# Kinen_Expansion.net
KiCad netlist of a schematic drawn in Altium Designer
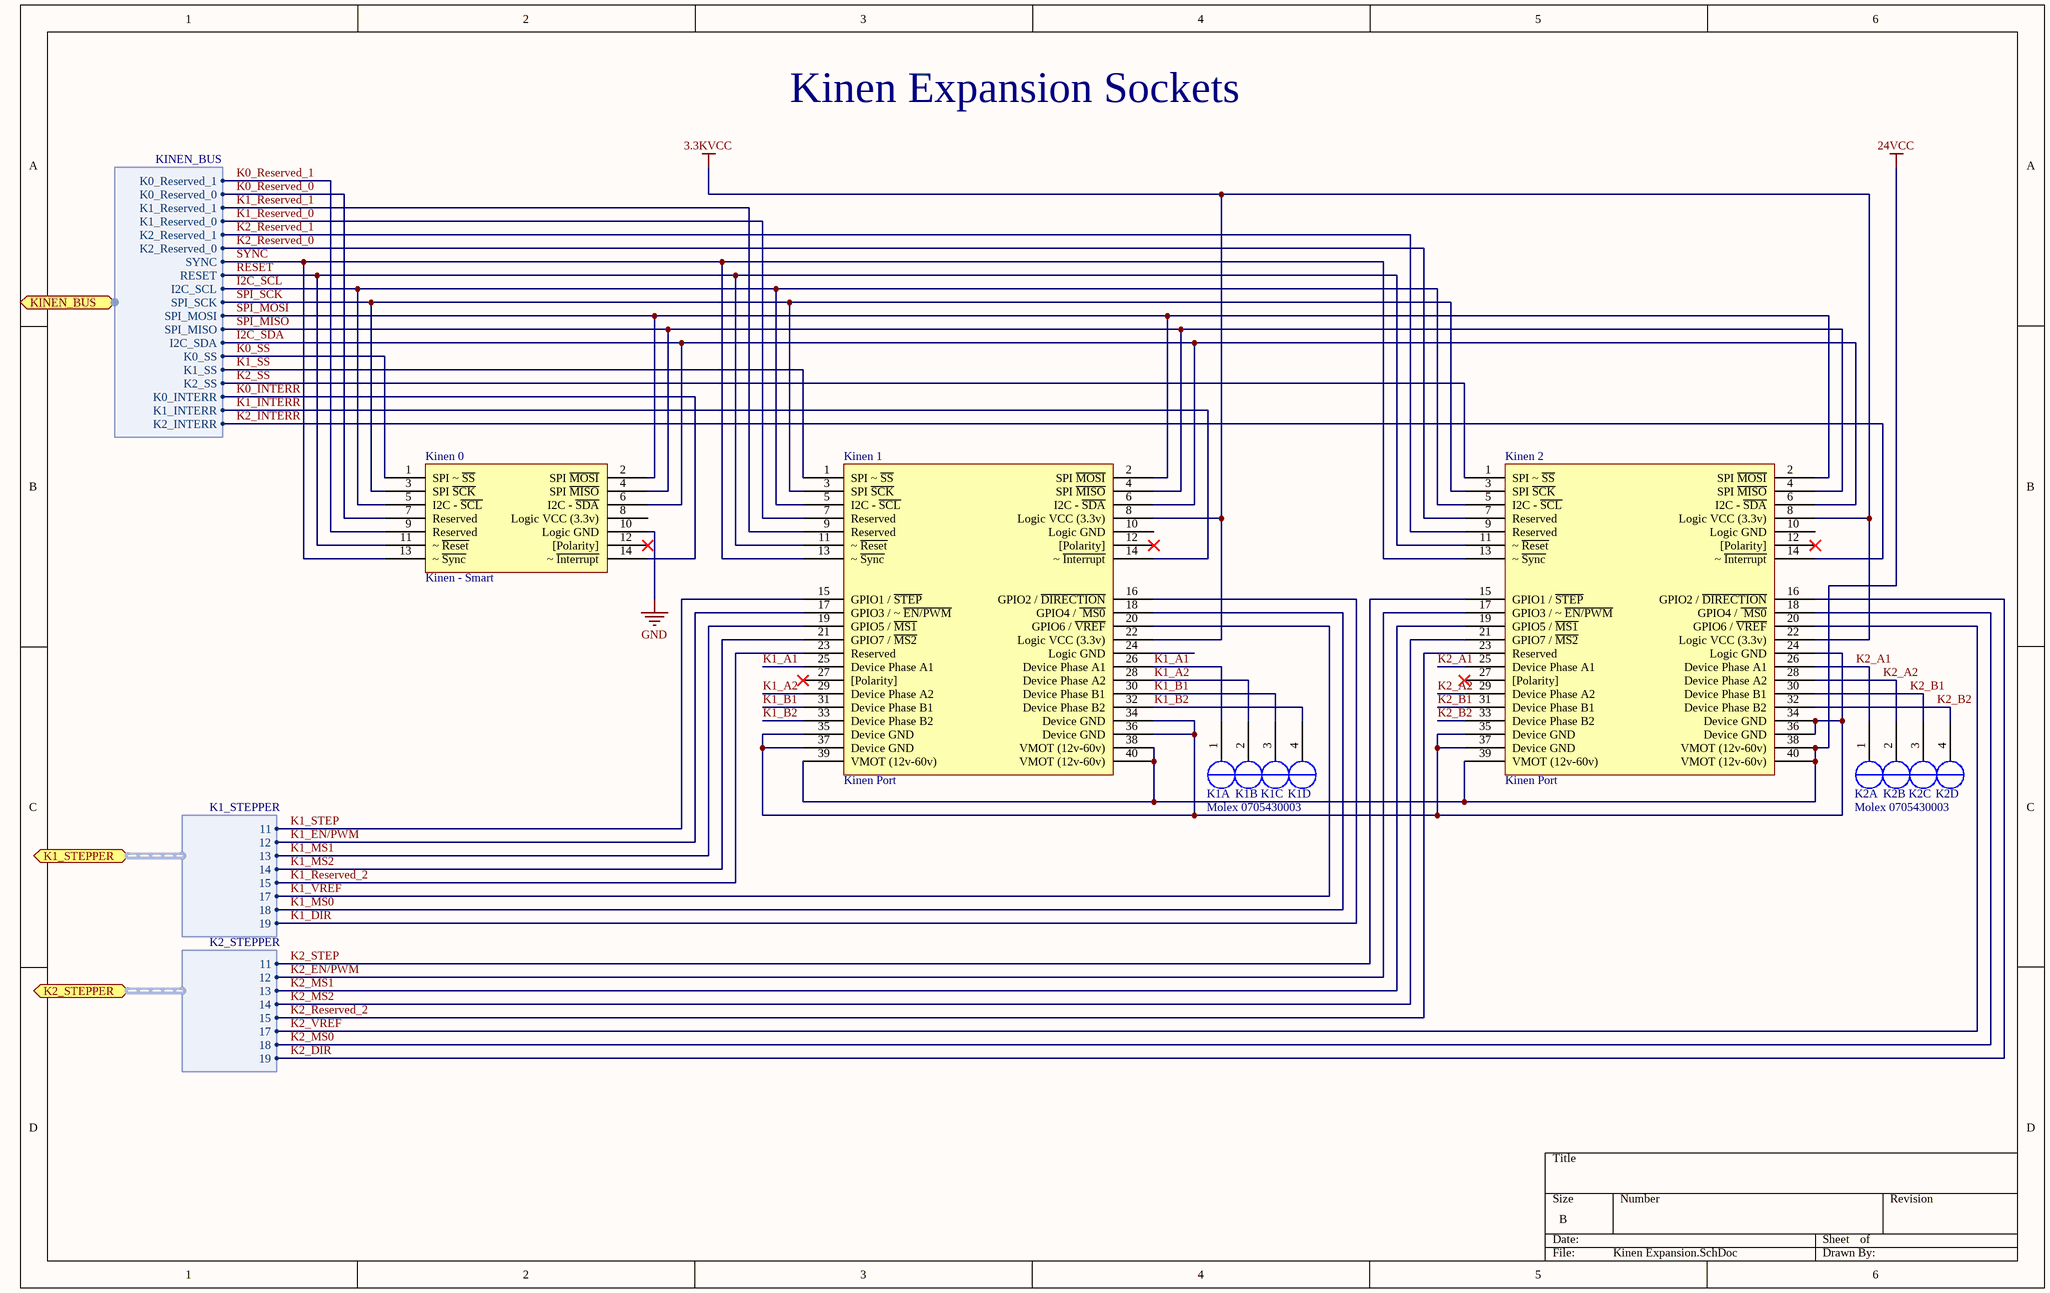
[diagram p0: Kinen Expansion.SchDoc]

(export (version "E")
  (design (tool "Eeschema 10.0.6"))
  (components
    (comp (ref "K1")
      (value "Molex 0705430003")
      (footprint "Molex 0705430003")
      (description "Molex 4 Pin Clip Connector")
      (libsource (lib "") (part "Molex 0705430003 Alt_3"))
    )
    (comp (ref "K2")
      (value "Molex 0705430003")
      (footprint "Molex 0705430003")
      (description "Molex 4 Pin Clip Connector")
      (libsource (lib "ZMBo Schematic Library") (part "Molex 0705430003 Alt"))
    )
    (comp (ref "Kinen 0")
      (value "Kinen - Smart")
      (footprint "Kinen Port - Smart - MOBO")
      (libsource (lib "ZMBo Schematic Library") (part "Kinen - Smart"))
    )
    (comp (ref "Kinen 1")
      (value "Kinen Port")
      (footprint "Kinen Port - MOBO")
      (libsource (lib "ZMBo Schematic Library") (part "Kinen Device NEW"))
    )
    (comp (ref "Kinen 2")
      (value "Kinen Port")
      (footprint "Kinen Port - MOBO")
      (libsource (lib "ZMBo Schematic Library") (part "Kinen Device NEW"))
    )
  )
  (nets
    (net (code "4") (name "/I2C_SCL") (class "Default")
      (node (ref "Kinen 0") (pin "5") (pinfunction "I2C_-_~{SCL}_5") (pintype "passive"))
      (node (ref "Kinen 1") (pin "5") (pinfunction "I2C_-_~{SCL}_5") (pintype "passive"))
      (node (ref "Kinen 2") (pin "5") (pinfunction "I2C_-_~{SCL}_5") (pintype "passive"))
    )
    (net (code "5") (name "/I2C_SDA") (class "Default")
      (node (ref "Kinen 0") (pin "6") (pinfunction "I2C_-_~{SDA}_6") (pintype "passive"))
      (node (ref "Kinen 1") (pin "6") (pinfunction "I2C_-_~{SDA}_6") (pintype "passive"))
      (node (ref "Kinen 2") (pin "6") (pinfunction "I2C_-_~{SDA}_6") (pintype "passive"))
    )
    (net (code "6") (name "/K0_INTERR") (class "Default")
      (node (ref "Kinen 0") (pin "14") (pinfunction "~_~{Interrupt}_14") (pintype "passive"))
    )
    (net (code "7") (name "/K0_Reserved_0") (class "Default")
      (node (ref "Kinen 0") (pin "7") (pinfunction "Reserved_7") (pintype "passive"))
    )
    (net (code "8") (name "/K0_Reserved_1") (class "Default")
      (node (ref "Kinen 0") (pin "9") (pinfunction "Reserved_9") (pintype "passive"))
    )
    (net (code "9") (name "/K0_SS") (class "Default")
      (node (ref "Kinen 0") (pin "1") (pinfunction "SPI_~_~{SS}_1") (pintype "passive"))
    )
    (net (code "10") (name "/K1_A1") (class "Default")
      (node (ref "K1") (pin "1") (pinfunction "OUT2B_1") (pintype "passive"))
      (node (ref "Kinen 1") (pin "25") (pinfunction "Device_Phase_A1_25") (pintype "passive"))
      (node (ref "Kinen 1") (pin "26") (pinfunction "Device_Phase_A1_26") (pintype "passive"))
    )
    (net (code "11") (name "/K1_A2") (class "Default")
      (node (ref "K1") (pin "2") (pinfunction "OUT2A_2") (pintype "passive"))
      (node (ref "Kinen 1") (pin "28") (pinfunction "Device_Phase_A2_28") (pintype "passive"))
      (node (ref "Kinen 1") (pin "29") (pinfunction "Device_Phase_A2_29") (pintype "passive"))
    )
    (net (code "12") (name "/K1_B1") (class "Default")
      (node (ref "K1") (pin "3") (pinfunction "OUT1A_3") (pintype "passive"))
      (node (ref "Kinen 1") (pin "30") (pinfunction "Device_Phase_B1_30") (pintype "passive"))
      (node (ref "Kinen 1") (pin "31") (pinfunction "Device_Phase_B1_31") (pintype "passive"))
    )
    (net (code "13") (name "/K1_B2") (class "Default")
      (node (ref "K1") (pin "4") (pinfunction "OUT1B_4") (pintype "passive"))
      (node (ref "Kinen 1") (pin "32") (pinfunction "Device_Phase_B2_32") (pintype "passive"))
      (node (ref "Kinen 1") (pin "33") (pinfunction "Device_Phase_B2_33") (pintype "passive"))
    )
    (net (code "14") (name "/K1_DIR") (class "Default")
      (node (ref "Kinen 1") (pin "16") (pinfunction "GPIO2_/_~{DIRECTION}_16") (pintype "passive"))
    )
    (net (code "15") (name "/K1_EN{slash}PWM") (class "Default")
      (node (ref "Kinen 1") (pin "17") (pinfunction "GPIO3_/_~_~{EN/PWM}_17") (pintype "passive"))
    )
    (net (code "16") (name "/K1_INTERR") (class "Default")
      (node (ref "Kinen 1") (pin "14") (pinfunction "~_~{Interrupt}_14") (pintype "passive"))
    )
    (net (code "17") (name "/K1_MS0") (class "Default")
      (node (ref "Kinen 1") (pin "18") (pinfunction "GPIO4_/_~{_MS0}_18") (pintype "passive"))
    )
    (net (code "18") (name "/K1_MS1") (class "Default")
      (node (ref "Kinen 1") (pin "19") (pinfunction "GPIO5_/_~{MS1}_19") (pintype "passive"))
    )
    (net (code "19") (name "/K1_MS2") (class "Default")
      (node (ref "Kinen 1") (pin "21") (pinfunction "GPIO7_/_~{MS2}_21") (pintype "passive"))
    )
    (net (code "20") (name "/K1_Reserved_0") (class "Default")
      (node (ref "Kinen 1") (pin "7") (pinfunction "Reserved_7") (pintype "passive"))
    )
    (net (code "21") (name "/K1_Reserved_1") (class "Default")
      (node (ref "Kinen 1") (pin "9") (pinfunction "Reserved_9") (pintype "passive"))
    )
    (net (code "22") (name "/K1_Reserved_2") (class "Default")
      (node (ref "Kinen 1") (pin "23") (pinfunction "Reserved_23") (pintype "passive"))
    )
    (net (code "23") (name "/K1_SS") (class "Default")
      (node (ref "Kinen 1") (pin "1") (pinfunction "SPI_~_~{SS}_1") (pintype "passive"))
    )
    (net (code "24") (name "/K1_STEP") (class "Default")
      (node (ref "Kinen 1") (pin "15") (pinfunction "GPIO1_/_~{STEP}_15") (pintype "passive"))
    )
    (net (code "25") (name "/K1_VREF") (class "Default")
      (node (ref "Kinen 1") (pin "20") (pinfunction "GPIO6_/_~{VREF}_20") (pintype "passive"))
    )
    (net (code "26") (name "/K2_A1") (class "Default")
      (node (ref "K2") (pin "1") (pinfunction "OUT2B_1") (pintype "passive"))
      (node (ref "Kinen 2") (pin "25") (pinfunction "Device_Phase_A1_25") (pintype "passive"))
      (node (ref "Kinen 2") (pin "26") (pinfunction "Device_Phase_A1_26") (pintype "passive"))
    )
    (net (code "27") (name "/K2_A2") (class "Default")
      (node (ref "K2") (pin "2") (pinfunction "OUT2A_2") (pintype "passive"))
      (node (ref "Kinen 2") (pin "28") (pinfunction "Device_Phase_A2_28") (pintype "passive"))
      (node (ref "Kinen 2") (pin "29") (pinfunction "Device_Phase_A2_29") (pintype "passive"))
    )
    (net (code "28") (name "/K2_B1") (class "Default")
      (node (ref "K2") (pin "3") (pinfunction "OUT1A_3") (pintype "passive"))
      (node (ref "Kinen 2") (pin "30") (pinfunction "Device_Phase_B1_30") (pintype "passive"))
      (node (ref "Kinen 2") (pin "31") (pinfunction "Device_Phase_B1_31") (pintype "passive"))
    )
    (net (code "29") (name "/K2_B2") (class "Default")
      (node (ref "K2") (pin "4") (pinfunction "OUT1B_4") (pintype "passive"))
      (node (ref "Kinen 2") (pin "32") (pinfunction "Device_Phase_B2_32") (pintype "passive"))
      (node (ref "Kinen 2") (pin "33") (pinfunction "Device_Phase_B2_33") (pintype "passive"))
    )
    (net (code "30") (name "/K2_DIR") (class "Default")
      (node (ref "Kinen 2") (pin "16") (pinfunction "GPIO2_/_~{DIRECTION}_16") (pintype "passive"))
    )
    (net (code "31") (name "/K2_EN{slash}PWM") (class "Default")
      (node (ref "Kinen 2") (pin "17") (pinfunction "GPIO3_/_~_~{EN/PWM}_17") (pintype "passive"))
    )
    (net (code "32") (name "/K2_INTERR") (class "Default")
      (node (ref "Kinen 2") (pin "14") (pinfunction "~_~{Interrupt}_14") (pintype "passive"))
    )
    (net (code "33") (name "/K2_MS0") (class "Default")
      (node (ref "Kinen 2") (pin "18") (pinfunction "GPIO4_/_~{_MS0}_18") (pintype "passive"))
    )
    (net (code "34") (name "/K2_MS1") (class "Default")
      (node (ref "Kinen 2") (pin "19") (pinfunction "GPIO5_/_~{MS1}_19") (pintype "passive"))
    )
    (net (code "35") (name "/K2_MS2") (class "Default")
      (node (ref "Kinen 2") (pin "21") (pinfunction "GPIO7_/_~{MS2}_21") (pintype "passive"))
    )
    (net (code "36") (name "/K2_Reserved_0") (class "Default")
      (node (ref "Kinen 2") (pin "7") (pinfunction "Reserved_7") (pintype "passive"))
    )
    (net (code "37") (name "/K2_Reserved_1") (class "Default")
      (node (ref "Kinen 2") (pin "9") (pinfunction "Reserved_9") (pintype "passive"))
    )
    (net (code "38") (name "/K2_Reserved_2") (class "Default")
      (node (ref "Kinen 2") (pin "23") (pinfunction "Reserved_23") (pintype "passive"))
    )
    (net (code "39") (name "/K2_SS") (class "Default")
      (node (ref "Kinen 2") (pin "1") (pinfunction "SPI_~_~{SS}_1") (pintype "passive"))
    )
    (net (code "40") (name "/K2_STEP") (class "Default")
      (node (ref "Kinen 2") (pin "15") (pinfunction "GPIO1_/_~{STEP}_15") (pintype "passive"))
    )
    (net (code "41") (name "/K2_VREF") (class "Default")
      (node (ref "Kinen 2") (pin "20") (pinfunction "GPIO6_/_~{VREF}_20") (pintype "passive"))
    )
    (net (code "42") (name "/RESET") (class "Default")
      (node (ref "Kinen 0") (pin "11") (pinfunction "~_~{Reset}_11") (pintype "passive"))
      (node (ref "Kinen 1") (pin "11") (pinfunction "~_~{Reset}_11") (pintype "passive"))
      (node (ref "Kinen 2") (pin "11") (pinfunction "~_~{Reset}_11") (pintype "passive"))
    )
    (net (code "43") (name "/SPI_MISO") (class "Default")
      (node (ref "Kinen 0") (pin "4") (pinfunction "SPI_~{MISO}_4") (pintype "passive"))
      (node (ref "Kinen 1") (pin "4") (pinfunction "SPI_~{MISO}_4") (pintype "passive"))
      (node (ref "Kinen 2") (pin "4") (pinfunction "SPI_~{MISO}_4") (pintype "passive"))
    )
    (net (code "44") (name "/SPI_MOSI") (class "Default")
      (node (ref "Kinen 0") (pin "2") (pinfunction "SPI_~{MOSI}_2") (pintype "passive"))
      (node (ref "Kinen 1") (pin "2") (pinfunction "SPI_~{MOSI}_2") (pintype "passive"))
      (node (ref "Kinen 2") (pin "2") (pinfunction "SPI_~{MOSI}_2") (pintype "passive"))
    )
    (net (code "45") (name "/SPI_SCK") (class "Default")
      (node (ref "Kinen 0") (pin "3") (pinfunction "SPI_~{SCK}_3") (pintype "passive"))
      (node (ref "Kinen 1") (pin "3") (pinfunction "SPI_~{SCK}_3") (pintype "passive"))
      (node (ref "Kinen 2") (pin "3") (pinfunction "SPI_~{SCK}_3") (pintype "passive"))
    )
    (net (code "46") (name "/SYNC") (class "Default")
      (node (ref "Kinen 0") (pin "13") (pinfunction "~_~{Sync}_13") (pintype "passive"))
      (node (ref "Kinen 1") (pin "13") (pinfunction "~_~{Sync}_13") (pintype "passive"))
      (node (ref "Kinen 2") (pin "13") (pinfunction "~_~{Sync}_13") (pintype "passive"))
    )
    (net (code "50") (name "3.3KVCC") (class "Default")
      (node (ref "Kinen 1") (pin "22") (pinfunction "Logic_VCC_(3.3v)_22") (pintype "passive"))
      (node (ref "Kinen 1") (pin "8") (pinfunction "Logic_VCC_(3.3v)_8") (pintype "passive"))
      (node (ref "Kinen 2") (pin "22") (pinfunction "Logic_VCC_(3.3v)_22") (pintype "passive"))
      (node (ref "Kinen 2") (pin "8") (pinfunction "Logic_VCC_(3.3v)_8") (pintype "passive"))
    )
    (net (code "51") (name "24VCC") (class "Default")
      (node (ref "Kinen 1") (pin "38") (pinfunction "VMOT_(12v-60v)_38") (pintype "passive"))
      (node (ref "Kinen 1") (pin "39") (pinfunction "VMOT_(12v-60v)_39") (pintype "passive"))
      (node (ref "Kinen 1") (pin "40") (pinfunction "VMOT_(12v-60v)_40") (pintype "passive"))
      (node (ref "Kinen 2") (pin "38") (pinfunction "VMOT_(12v-60v)_38") (pintype "passive"))
      (node (ref "Kinen 2") (pin "39") (pinfunction "VMOT_(12v-60v)_39") (pintype "passive"))
      (node (ref "Kinen 2") (pin "40") (pinfunction "VMOT_(12v-60v)_40") (pintype "passive"))
    )
    (net (code "52") (name "GND") (class "Default")
      (node (ref "Kinen 0") (pin "10") (pinfunction "Logic_GND_10") (pintype "passive"))
    )
    (net (code "53") (name "Net-(Kinen 1-Device_GND-Pad34)") (class "Default")
      (node (ref "Kinen 1") (pin "34") (pinfunction "Device_GND_34") (pintype "passive"))
      (node (ref "Kinen 1") (pin "35") (pinfunction "Device_GND_35") (pintype "passive"))
      (node (ref "Kinen 1") (pin "36") (pinfunction "Device_GND_36") (pintype "passive"))
      (node (ref "Kinen 1") (pin "37") (pinfunction "Device_GND_37") (pintype "passive"))
      (node (ref "Kinen 2") (pin "24") (pinfunction "Logic_GND_24") (pintype "passive"))
      (node (ref "Kinen 2") (pin "34") (pinfunction "Device_GND_34") (pintype "passive"))
      (node (ref "Kinen 2") (pin "35") (pinfunction "Device_GND_35") (pintype "passive"))
      (node (ref "Kinen 2") (pin "36") (pinfunction "Device_GND_36") (pintype "passive"))
      (node (ref "Kinen 2") (pin "37") (pinfunction "Device_GND_37") (pintype "passive"))
    )
    (net (code "54") (name "unconnected-(Kinen 0-Logic_VCC_(3.3v)-Pad8)") (class "Default")
      (node (ref "Kinen 0") (pin "8") (pinfunction "Logic_VCC_(3.3v)_8") (pintype "passive"))
    )
    (net (code "55") (name "unconnected-(Kinen 0-[Polarity]-Pad12)") (class "Default")
      (node (ref "Kinen 0") (pin "12") (pinfunction "[Polarity]_12") (pintype "passive+no_connect"))
    )
    (net (code "56") (name "unconnected-(Kinen 1-Logic_GND-Pad10)") (class "Default")
      (node (ref "Kinen 1") (pin "10") (pinfunction "Logic_GND_10") (pintype "passive"))
    )
    (net (code "57") (name "unconnected-(Kinen 1-Logic_GND-Pad24)") (class "Default")
      (node (ref "Kinen 1") (pin "24") (pinfunction "Logic_GND_24") (pintype "passive"))
    )
    (net (code "58") (name "unconnected-(Kinen 1-[Polarity]-Pad12)") (class "Default")
      (node (ref "Kinen 1") (pin "12") (pinfunction "[Polarity]_12") (pintype "passive+no_connect"))
    )
    (net (code "59") (name "unconnected-(Kinen 1-[Polarity]-Pad27)") (class "Default")
      (node (ref "Kinen 1") (pin "27") (pinfunction "[Polarity]_27") (pintype "passive+no_connect"))
    )
    (net (code "60") (name "unconnected-(Kinen 2-Logic_GND-Pad10)") (class "Default")
      (node (ref "Kinen 2") (pin "10") (pinfunction "Logic_GND_10") (pintype "passive"))
    )
    (net (code "61") (name "unconnected-(Kinen 2-[Polarity]-Pad12)") (class "Default")
      (node (ref "Kinen 2") (pin "12") (pinfunction "[Polarity]_12") (pintype "passive+no_connect"))
    )
    (net (code "62") (name "unconnected-(Kinen 2-[Polarity]-Pad27)") (class "Default")
      (node (ref "Kinen 2") (pin "27") (pinfunction "[Polarity]_27") (pintype "passive+no_connect"))
    )
  )
)
